# Breakout.net
KiCad netlist of a schematic drawn in Altium Designer
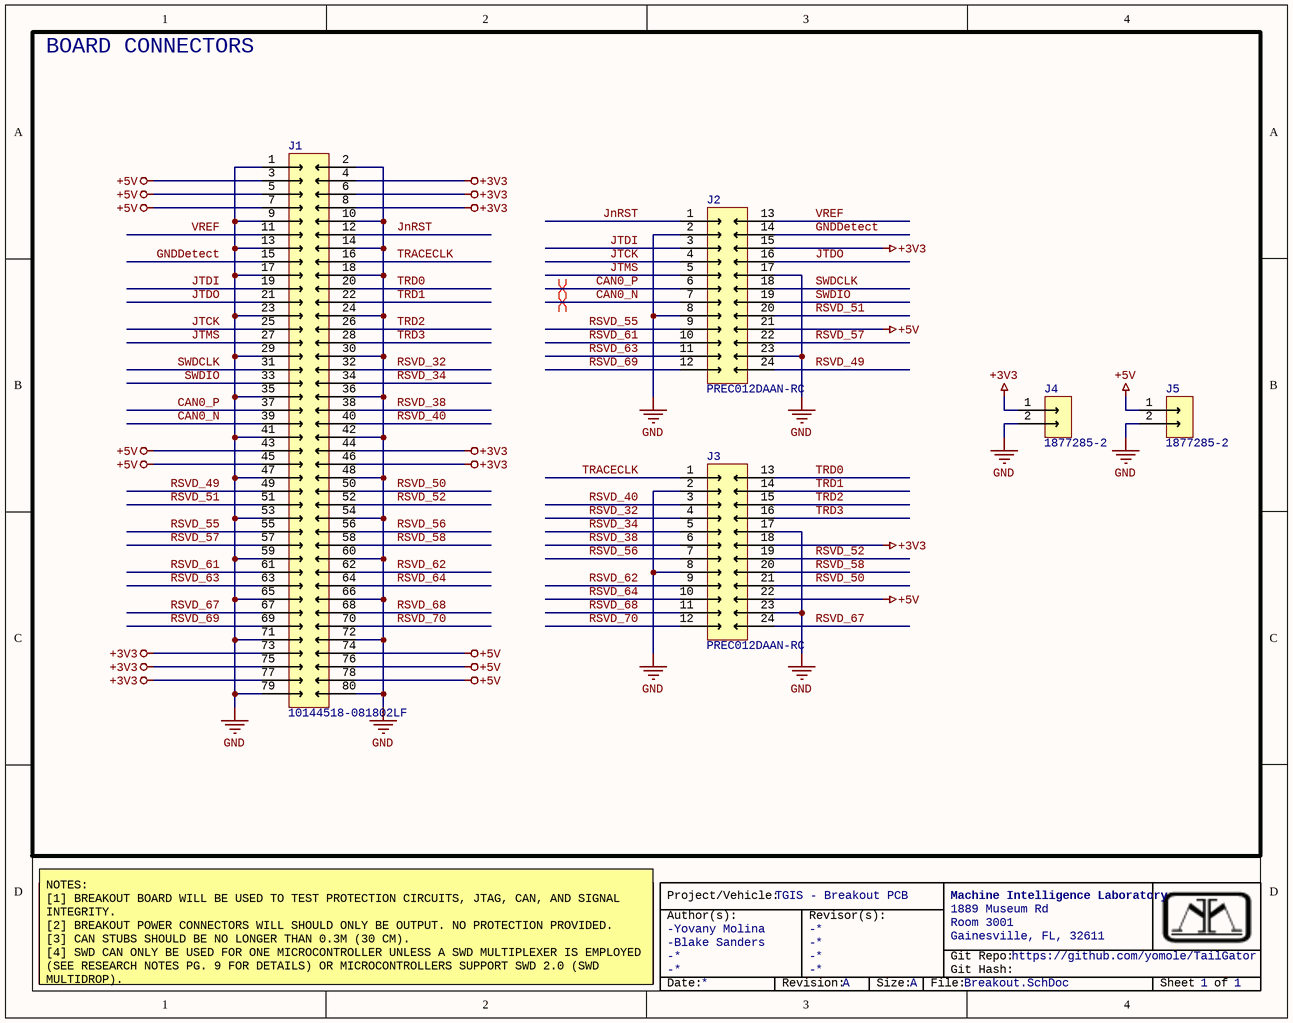
[diagram p0: Breakout.SchDoc]

(export (version "E")
  (design (tool "Eeschema 10.0.6"))
  (components
    (comp (ref "J1")
      (value "10144518-081802LF")
      (footprint "AMPHENOL_10144518-081802LF")
      (description "CONN PLUG 1 80POS SMD GOLD")
      (libsource (lib "TGIS") (part "10144518-081802LF"))
    )
    (comp (ref "J2")
      (value "PREC012DAAN-RC")
      (footprint "PREC012DAAN-RC")
      (description "Connector Header Through Hole 24 position 0.100\" (2.54mm)")
      (libsource (lib "TGIS") (part "PREC012DAAN-RC"))
    )
    (comp (ref "J3")
      (value "PREC012DAAN-RC")
      (footprint "PREC012DAAN-RC")
      (description "Connector Header Through Hole 24 position 0.100\" (2.54mm)")
      (libsource (lib "TGIS") (part "PREC012DAAN-RC"))
    )
    (comp (ref "J4")
      (value "1877285-2")
      (footprint "TE_1877285-2")
      (libsource (lib "TGIS") (part "1877285-2"))
    )
    (comp (ref "J5")
      (value "1877285-2")
      (footprint "TE_1877285-2")
      (libsource (lib "TGIS") (part "1877285-2"))
    )
  )
  (nets
    (net (code "1") (name "+3V3") (class "Default")
      (node (ref "J1") (pin "4") (pinfunction "4_4") (pintype "passive"))
      (node (ref "J1") (pin "44") (pinfunction "44_44") (pintype "passive"))
      (node (ref "J1") (pin "46") (pinfunction "46_46") (pintype "passive"))
      (node (ref "J1") (pin "6") (pinfunction "6_6") (pintype "passive"))
      (node (ref "J1") (pin "73") (pinfunction "73_73") (pintype "passive"))
      (node (ref "J1") (pin "75") (pinfunction "75_75") (pintype "passive"))
      (node (ref "J1") (pin "77") (pinfunction "77_77") (pintype "passive"))
      (node (ref "J1") (pin "8") (pinfunction "8_8") (pintype "passive"))
      (node (ref "J2") (pin "15") (pinfunction "15_15") (pintype "passive"))
      (node (ref "J3") (pin "18") (pinfunction "18_18") (pintype "passive"))
      (node (ref "J4") (pin "1") (pinfunction "1_1") (pintype "passive"))
    )
    (net (code "2") (name "+5V") (class "Default")
      (node (ref "J1") (pin "3") (pinfunction "3_3") (pintype "passive"))
      (node (ref "J1") (pin "43") (pinfunction "43_43") (pintype "passive"))
      (node (ref "J1") (pin "45") (pinfunction "45_45") (pintype "passive"))
      (node (ref "J1") (pin "5") (pinfunction "5_5") (pintype "passive"))
      (node (ref "J1") (pin "7") (pinfunction "7_7") (pintype "passive"))
      (node (ref "J1") (pin "74") (pinfunction "74_74") (pintype "passive"))
      (node (ref "J1") (pin "76") (pinfunction "76_76") (pintype "passive"))
      (node (ref "J1") (pin "78") (pinfunction "78_78") (pintype "passive"))
      (node (ref "J2") (pin "21") (pinfunction "21_21") (pintype "passive"))
      (node (ref "J3") (pin "22") (pinfunction "22_22") (pintype "passive"))
      (node (ref "J5") (pin "1") (pinfunction "1_1") (pintype "passive"))
    )
    (net (code "3") (name "/CAN0_N") (class "Default")
      (node (ref "J1") (pin "39") (pinfunction "39_39") (pintype "passive"))
      (node (ref "J2") (pin "7") (pinfunction "7_7") (pintype "passive"))
    )
    (net (code "4") (name "/CAN0_P") (class "Default")
      (node (ref "J1") (pin "37") (pinfunction "37_37") (pintype "passive"))
      (node (ref "J2") (pin "6") (pinfunction "6_6") (pintype "passive"))
    )
    (net (code "5") (name "/GNDDetect") (class "Default")
      (node (ref "J1") (pin "15") (pinfunction "15_15") (pintype "passive"))
      (node (ref "J2") (pin "14") (pinfunction "14_14") (pintype "passive"))
    )
    (net (code "6") (name "/JTCK") (class "Default")
      (node (ref "J1") (pin "25") (pinfunction "25_25") (pintype "passive"))
      (node (ref "J2") (pin "4") (pinfunction "4_4") (pintype "passive"))
    )
    (net (code "7") (name "/JTDI") (class "Default")
      (node (ref "J1") (pin "19") (pinfunction "19_19") (pintype "passive"))
      (node (ref "J2") (pin "3") (pinfunction "3_3") (pintype "passive"))
    )
    (net (code "8") (name "/JTDO") (class "Default")
      (node (ref "J1") (pin "21") (pinfunction "21_21") (pintype "passive"))
      (node (ref "J2") (pin "16") (pinfunction "16_16") (pintype "passive"))
    )
    (net (code "9") (name "/JTMS") (class "Default")
      (node (ref "J1") (pin "27") (pinfunction "27_27") (pintype "passive"))
      (node (ref "J2") (pin "5") (pinfunction "5_5") (pintype "passive"))
    )
    (net (code "10") (name "/JnRST") (class "Default")
      (node (ref "J1") (pin "12") (pinfunction "12_12") (pintype "passive"))
      (node (ref "J2") (pin "1") (pinfunction "1_1") (pintype "passive"))
    )
    (net (code "11") (name "/RSVD_32") (class "Default")
      (node (ref "J1") (pin "32") (pinfunction "32_32") (pintype "passive"))
      (node (ref "J3") (pin "4") (pinfunction "4_4") (pintype "passive"))
    )
    (net (code "12") (name "/RSVD_34") (class "Default")
      (node (ref "J1") (pin "34") (pinfunction "34_34") (pintype "passive"))
      (node (ref "J3") (pin "5") (pinfunction "5_5") (pintype "passive"))
    )
    (net (code "13") (name "/RSVD_38") (class "Default")
      (node (ref "J1") (pin "38") (pinfunction "38_38") (pintype "passive"))
      (node (ref "J3") (pin "6") (pinfunction "6_6") (pintype "passive"))
    )
    (net (code "14") (name "/RSVD_40") (class "Default")
      (node (ref "J1") (pin "40") (pinfunction "40_40") (pintype "passive"))
      (node (ref "J3") (pin "3") (pinfunction "3_3") (pintype "passive"))
    )
    (net (code "15") (name "/RSVD_49") (class "Default")
      (node (ref "J1") (pin "49") (pinfunction "49_49") (pintype "passive"))
      (node (ref "J2") (pin "24") (pinfunction "24_24") (pintype "passive"))
    )
    (net (code "16") (name "/RSVD_50") (class "Default")
      (node (ref "J1") (pin "50") (pinfunction "50_50") (pintype "passive"))
      (node (ref "J3") (pin "21") (pinfunction "21_21") (pintype "passive"))
    )
    (net (code "17") (name "/RSVD_51") (class "Default")
      (node (ref "J1") (pin "51") (pinfunction "51_51") (pintype "passive"))
      (node (ref "J2") (pin "20") (pinfunction "20_20") (pintype "passive"))
    )
    (net (code "18") (name "/RSVD_52") (class "Default")
      (node (ref "J1") (pin "52") (pinfunction "52_52") (pintype "passive"))
      (node (ref "J3") (pin "19") (pinfunction "19_19") (pintype "passive"))
    )
    (net (code "19") (name "/RSVD_55") (class "Default")
      (node (ref "J1") (pin "55") (pinfunction "55_55") (pintype "passive"))
      (node (ref "J2") (pin "9") (pinfunction "9_9") (pintype "passive"))
    )
    (net (code "20") (name "/RSVD_56") (class "Default")
      (node (ref "J1") (pin "56") (pinfunction "56_56") (pintype "passive"))
      (node (ref "J3") (pin "7") (pinfunction "7_7") (pintype "passive"))
    )
    (net (code "21") (name "/RSVD_57") (class "Default")
      (node (ref "J1") (pin "57") (pinfunction "57_57") (pintype "passive"))
      (node (ref "J2") (pin "22") (pinfunction "22_22") (pintype "passive"))
    )
    (net (code "22") (name "/RSVD_58") (class "Default")
      (node (ref "J1") (pin "58") (pinfunction "58_58") (pintype "passive"))
      (node (ref "J3") (pin "20") (pinfunction "20_20") (pintype "passive"))
    )
    (net (code "23") (name "/RSVD_61") (class "Default")
      (node (ref "J1") (pin "61") (pinfunction "61_61") (pintype "passive"))
      (node (ref "J2") (pin "10") (pinfunction "10_10") (pintype "passive"))
    )
    (net (code "24") (name "/RSVD_62") (class "Default")
      (node (ref "J1") (pin "62") (pinfunction "62_62") (pintype "passive"))
      (node (ref "J3") (pin "9") (pinfunction "9_9") (pintype "passive"))
    )
    (net (code "25") (name "/RSVD_63") (class "Default")
      (node (ref "J1") (pin "63") (pinfunction "63_63") (pintype "passive"))
      (node (ref "J2") (pin "11") (pinfunction "11_11") (pintype "passive"))
    )
    (net (code "26") (name "/RSVD_64") (class "Default")
      (node (ref "J1") (pin "64") (pinfunction "64_64") (pintype "passive"))
      (node (ref "J3") (pin "10") (pinfunction "10_10") (pintype "passive"))
    )
    (net (code "27") (name "/RSVD_67") (class "Default")
      (node (ref "J1") (pin "67") (pinfunction "67_67") (pintype "passive"))
      (node (ref "J3") (pin "24") (pinfunction "24_24") (pintype "passive"))
    )
    (net (code "28") (name "/RSVD_68") (class "Default")
      (node (ref "J1") (pin "68") (pinfunction "68_68") (pintype "passive"))
      (node (ref "J3") (pin "11") (pinfunction "11_11") (pintype "passive"))
    )
    (net (code "29") (name "/RSVD_69") (class "Default")
      (node (ref "J1") (pin "69") (pinfunction "69_69") (pintype "passive"))
      (node (ref "J2") (pin "12") (pinfunction "12_12") (pintype "passive"))
    )
    (net (code "30") (name "/RSVD_70") (class "Default")
      (node (ref "J1") (pin "70") (pinfunction "70_70") (pintype "passive"))
      (node (ref "J3") (pin "12") (pinfunction "12_12") (pintype "passive"))
    )
    (net (code "31") (name "/SWDCLK") (class "Default")
      (node (ref "J1") (pin "31") (pinfunction "31_31") (pintype "passive"))
      (node (ref "J2") (pin "18") (pinfunction "18_18") (pintype "passive"))
    )
    (net (code "32") (name "/SWDIO") (class "Default")
      (node (ref "J1") (pin "33") (pinfunction "33_33") (pintype "passive"))
      (node (ref "J2") (pin "19") (pinfunction "19_19") (pintype "passive"))
    )
    (net (code "33") (name "/TRACECLK") (class "Default")
      (node (ref "J1") (pin "16") (pinfunction "16_16") (pintype "passive"))
      (node (ref "J3") (pin "1") (pinfunction "1_1") (pintype "passive"))
    )
    (net (code "34") (name "/TRD0") (class "Default")
      (node (ref "J1") (pin "20") (pinfunction "20_20") (pintype "passive"))
      (node (ref "J3") (pin "13") (pinfunction "13_13") (pintype "passive"))
    )
    (net (code "35") (name "/TRD1") (class "Default")
      (node (ref "J1") (pin "22") (pinfunction "22_22") (pintype "passive"))
      (node (ref "J3") (pin "14") (pinfunction "14_14") (pintype "passive"))
    )
    (net (code "36") (name "/TRD2") (class "Default")
      (node (ref "J1") (pin "26") (pinfunction "26_26") (pintype "passive"))
      (node (ref "J3") (pin "15") (pinfunction "15_15") (pintype "passive"))
    )
    (net (code "37") (name "/TRD3") (class "Default")
      (node (ref "J1") (pin "28") (pinfunction "28_28") (pintype "passive"))
      (node (ref "J3") (pin "16") (pinfunction "16_16") (pintype "passive"))
    )
    (net (code "38") (name "/VREF") (class "Default")
      (node (ref "J1") (pin "11") (pinfunction "11_11") (pintype "passive"))
      (node (ref "J2") (pin "13") (pinfunction "13_13") (pintype "passive"))
    )
    (net (code "39") (name "GND") (class "Default")
      (node (ref "J1") (pin "1") (pinfunction "1_1") (pintype "passive"))
      (node (ref "J1") (pin "10") (pinfunction "10_10") (pintype "passive"))
      (node (ref "J1") (pin "13") (pinfunction "13_13") (pintype "passive"))
      (node (ref "J1") (pin "14") (pinfunction "14_14") (pintype "passive"))
      (node (ref "J1") (pin "17") (pinfunction "17_17") (pintype "passive"))
      (node (ref "J1") (pin "18") (pinfunction "18_18") (pintype "passive"))
      (node (ref "J1") (pin "2") (pinfunction "2_2") (pintype "passive"))
      (node (ref "J1") (pin "23") (pinfunction "23_23") (pintype "passive"))
      (node (ref "J1") (pin "24") (pinfunction "24_24") (pintype "passive"))
      (node (ref "J1") (pin "29") (pinfunction "29_29") (pintype "passive"))
      (node (ref "J1") (pin "30") (pinfunction "30_30") (pintype "passive"))
      (node (ref "J1") (pin "35") (pinfunction "35_35") (pintype "passive"))
      (node (ref "J1") (pin "36") (pinfunction "36_36") (pintype "passive"))
      (node (ref "J1") (pin "41") (pinfunction "41_41") (pintype "passive"))
      (node (ref "J1") (pin "42") (pinfunction "42_42") (pintype "passive"))
      (node (ref "J1") (pin "47") (pinfunction "47_47") (pintype "passive"))
      (node (ref "J1") (pin "48") (pinfunction "48_48") (pintype "passive"))
      (node (ref "J1") (pin "53") (pinfunction "53_53") (pintype "passive"))
      (node (ref "J1") (pin "54") (pinfunction "54_54") (pintype "passive"))
      (node (ref "J1") (pin "59") (pinfunction "59_59") (pintype "passive"))
      (node (ref "J1") (pin "60") (pinfunction "60_60") (pintype "passive"))
      (node (ref "J1") (pin "65") (pinfunction "65_65") (pintype "passive"))
      (node (ref "J1") (pin "66") (pinfunction "66_66") (pintype "passive"))
      (node (ref "J1") (pin "71") (pinfunction "71_71") (pintype "passive"))
      (node (ref "J1") (pin "72") (pinfunction "72_72") (pintype "passive"))
      (node (ref "J1") (pin "79") (pinfunction "79_79") (pintype "passive"))
      (node (ref "J1") (pin "80") (pinfunction "80_80") (pintype "passive"))
      (node (ref "J1") (pin "9") (pinfunction "9_9") (pintype "passive"))
      (node (ref "J2") (pin "17") (pinfunction "17_17") (pintype "passive"))
      (node (ref "J2") (pin "2") (pinfunction "2_2") (pintype "passive"))
      (node (ref "J2") (pin "23") (pinfunction "23_23") (pintype "passive"))
      (node (ref "J2") (pin "8") (pinfunction "8_8") (pintype "passive"))
      (node (ref "J3") (pin "17") (pinfunction "17_17") (pintype "passive"))
      (node (ref "J3") (pin "2") (pinfunction "2_2") (pintype "passive"))
      (node (ref "J3") (pin "23") (pinfunction "23_23") (pintype "passive"))
      (node (ref "J3") (pin "8") (pinfunction "8_8") (pintype "passive"))
      (node (ref "J4") (pin "2") (pinfunction "2_2") (pintype "passive"))
      (node (ref "J5") (pin "2") (pinfunction "2_2") (pintype "passive"))
    )
  )
)
